# PCB-ARD-DUEBOS.net
KiCad netlist of a schematic drawn in EAGLE
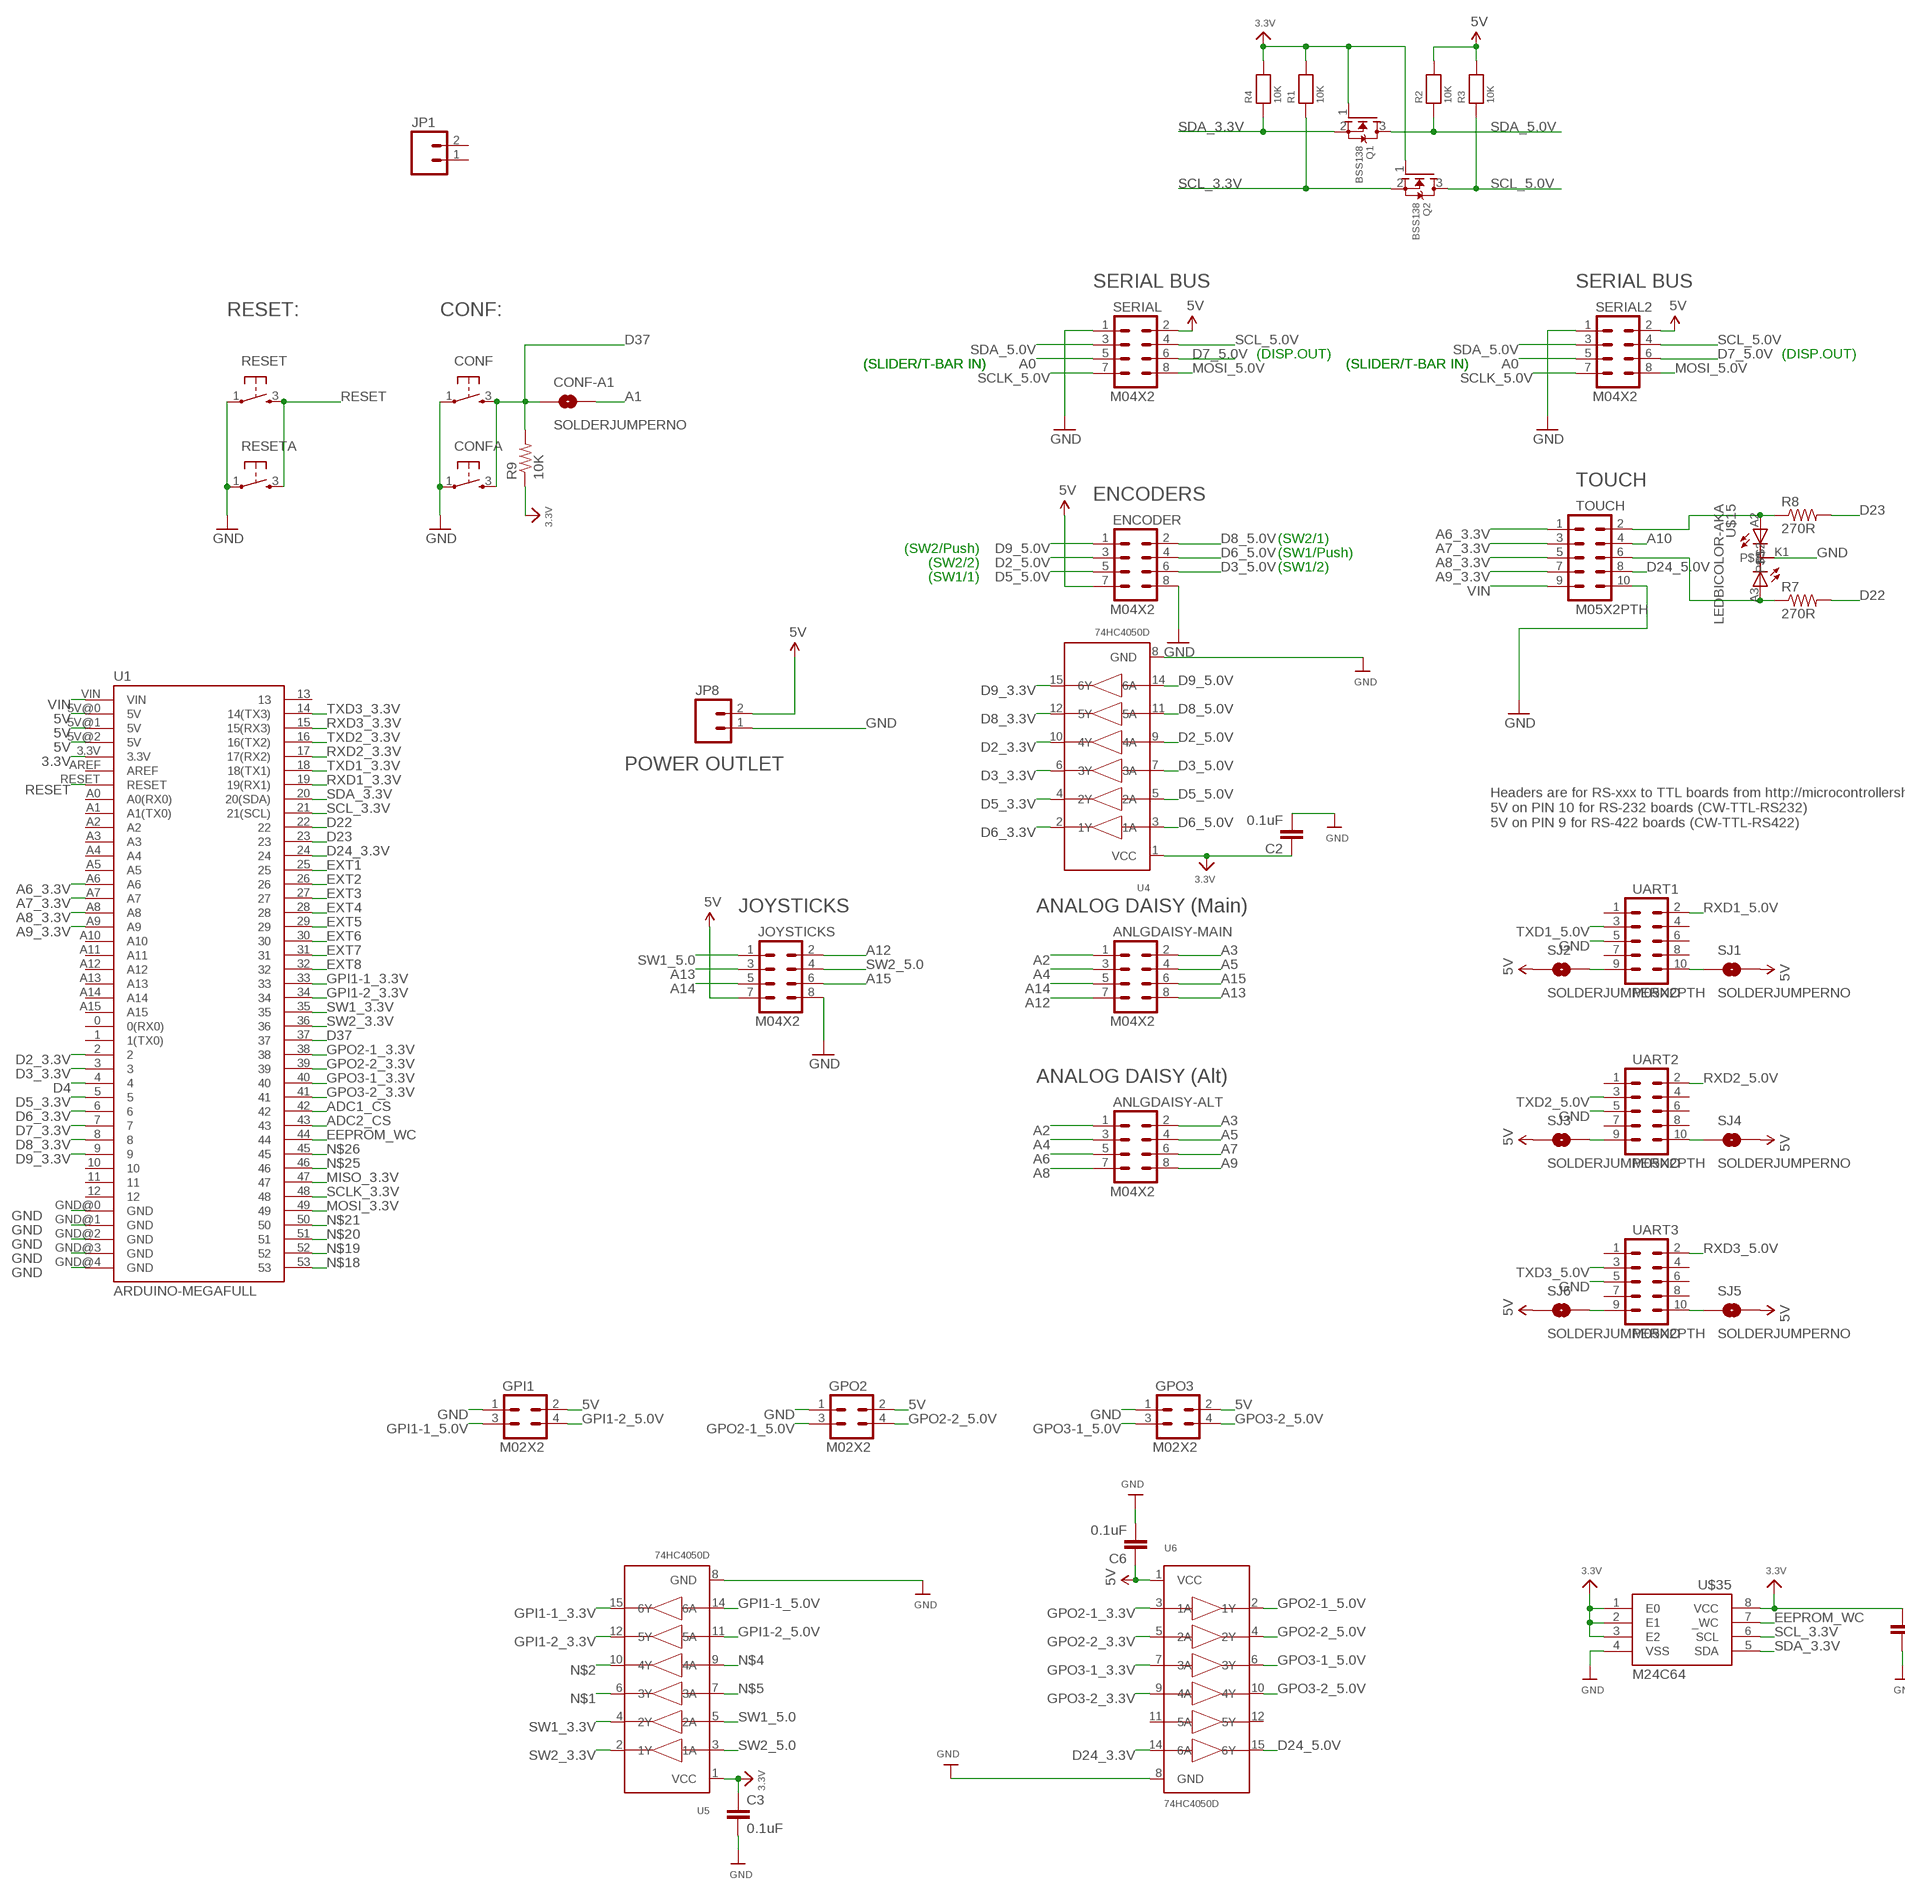
[diagram p0: schematic, sheet 1, part 1 of 2]
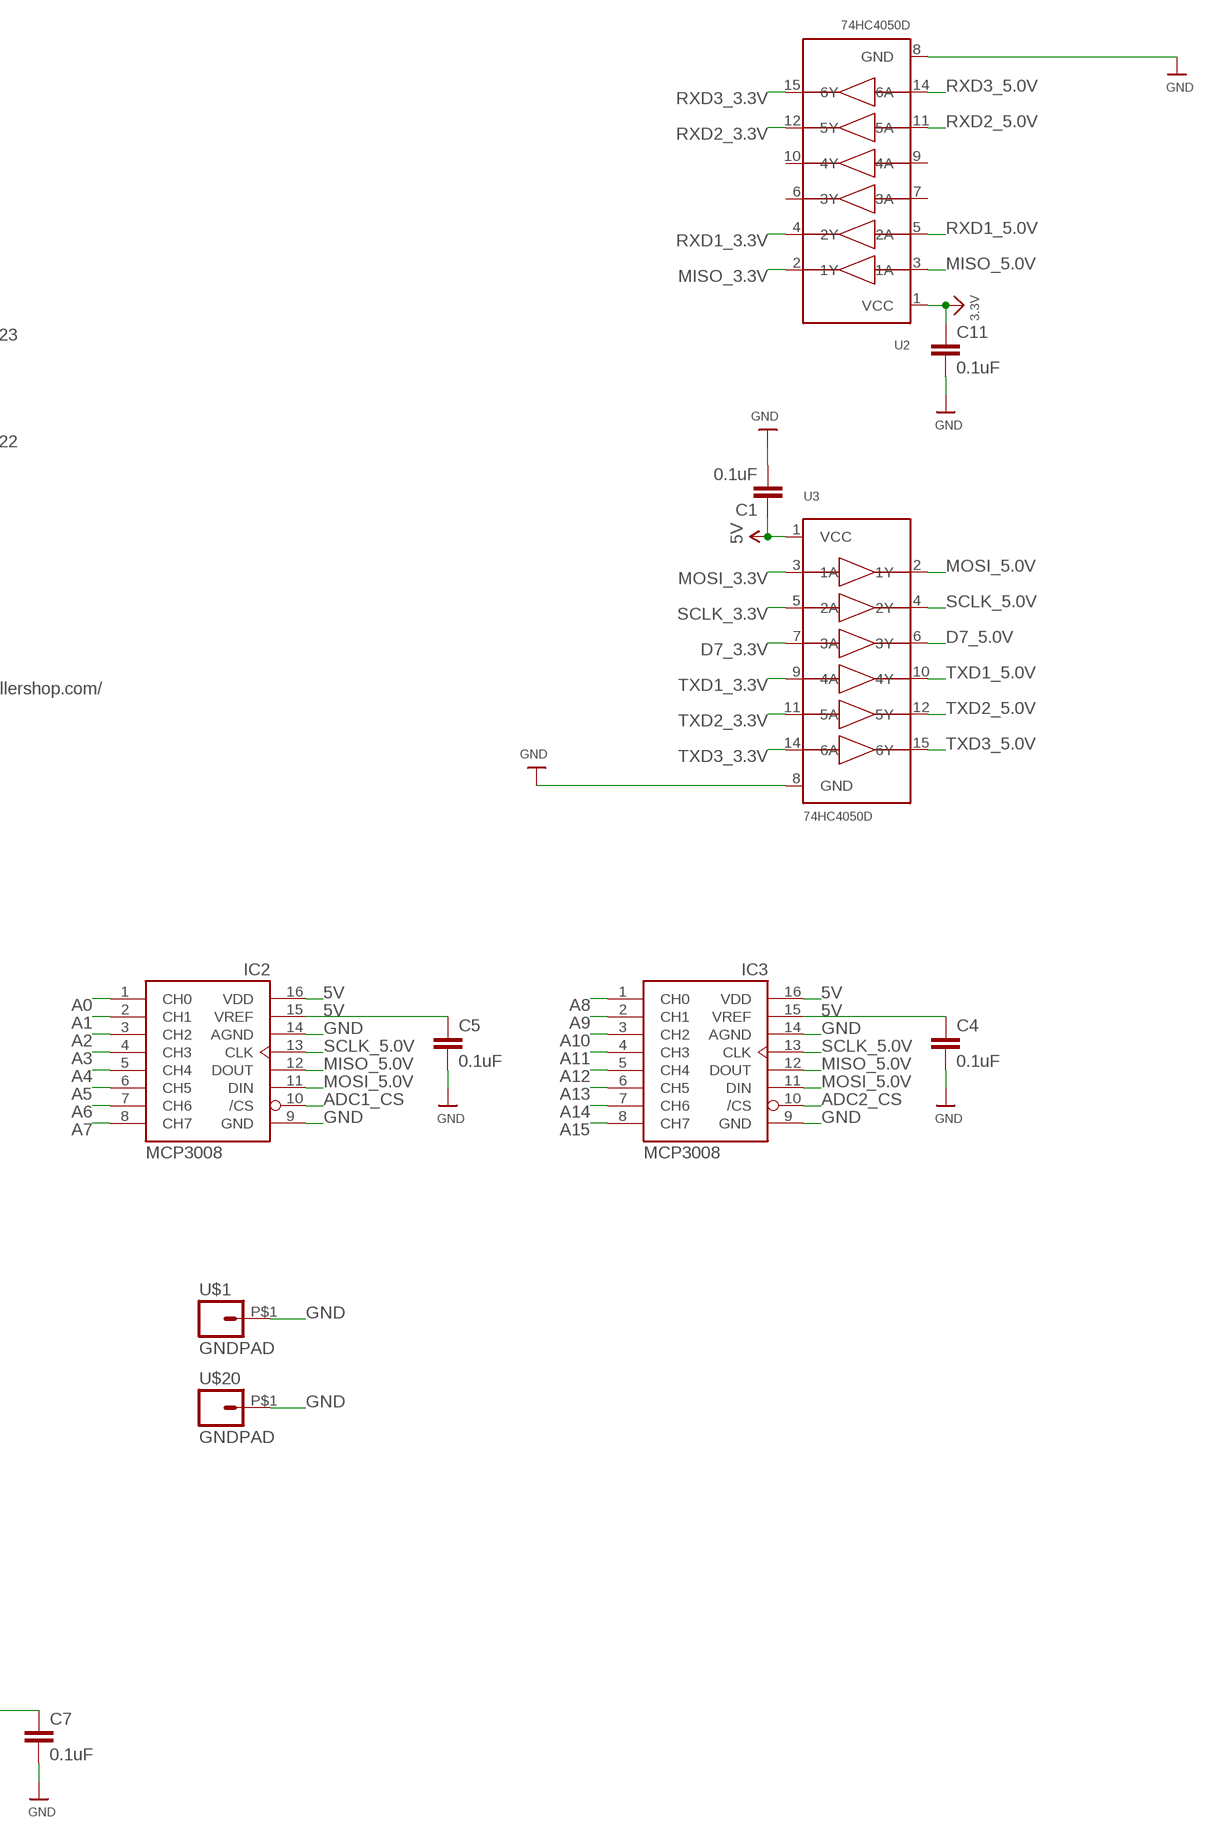
[diagram p1: schematic, sheet 1, part 2 of 2]

(export (version "E")
  (design (tool "Eeschema 10.0.6"))
  (components
    (comp (ref "ANLGDAISY-ALT")
      (value "M04X2")
      (footprint "eagle-import:2X4")
      (libsource (lib "eagle-import") (part "M04X2"))
    )
    (comp (ref "ANLGDAISY-MAIN")
      (value "M04X2")
      (footprint "eagle-import:2X4")
      (libsource (lib "eagle-import") (part "M04X2"))
    )
    (comp (ref "C1")
      (value "0.1uF")
      (footprint "eagle-import:0603-CAP")
      (libsource (lib "eagle-import") (part "CAP0603-CAP"))
    )
    (comp (ref "C2")
      (value "0.1uF")
      (footprint "eagle-import:0603-CAP")
      (libsource (lib "eagle-import") (part "CAP0603-CAP"))
    )
    (comp (ref "C3")
      (value "0.1uF")
      (footprint "eagle-import:0603-CAP")
      (libsource (lib "eagle-import") (part "CAP0603-CAP"))
    )
    (comp (ref "C4")
      (value "0.1uF")
      (footprint "eagle-import:0603-CAP")
      (libsource (lib "eagle-import") (part "CAP0603-CAP"))
    )
    (comp (ref "C5")
      (value "0.1uF")
      (footprint "eagle-import:0603-CAP")
      (libsource (lib "eagle-import") (part "CAP0603-CAP"))
    )
    (comp (ref "C6")
      (value "0.1uF")
      (footprint "eagle-import:0603-CAP")
      (libsource (lib "eagle-import") (part "CAP0603-CAP"))
    )
    (comp (ref "C7")
      (value "0.1uF")
      (footprint "eagle-import:0603-CAP")
      (libsource (lib "eagle-import") (part "CAP0603-CAP"))
    )
    (comp (ref "C11")
      (value "0.1uF")
      (footprint "eagle-import:0603-CAP")
      (libsource (lib "eagle-import") (part "CAP0603-CAP"))
    )
    (comp (ref "CONF")
      (value "TAC_SWITCH")
      (footprint "eagle-import:PUSHBUTTON")
      (libsource (lib "eagle-import") (part "TAC_SWITCH"))
    )
    (comp (ref "CONF-A1")
      (value "SOLDERJUMPERNO")
      (footprint "eagle-import:SJ_2S-NO")
      (libsource (lib "eagle-import") (part "SOLDERJUMPERNO"))
    )
    (comp (ref "CONFA")
      (value "TAC_SWITCH")
      (footprint "eagle-import:PUSHBUTTON")
      (libsource (lib "eagle-import") (part "TAC_SWITCH"))
    )
    (comp (ref "ENCODER")
      (value "M04X2")
      (footprint "eagle-import:2X4")
      (libsource (lib "eagle-import") (part "M04X2"))
    )
    (comp (ref "GPI1")
      (value "M02X2")
      (footprint "eagle-import:2X2")
      (libsource (lib "eagle-import") (part "M02X2"))
    )
    (comp (ref "GPO2")
      (value "M02X2")
      (footprint "eagle-import:2X2")
      (libsource (lib "eagle-import") (part "M02X2"))
    )
    (comp (ref "GPO3")
      (value "M02X2")
      (footprint "eagle-import:2X2")
      (libsource (lib "eagle-import") (part "M02X2"))
    )
    (comp (ref "IC2")
      (value "MCP3008SOIC")
      (footprint "eagle-import:SOIC16")
      (libsource (lib "eagle-import") (part "MCP3008SOIC"))
    )
    (comp (ref "IC3")
      (value "MCP3008SOIC")
      (footprint "eagle-import:SOIC16")
      (libsource (lib "eagle-import") (part "MCP3008SOIC"))
    )
    (comp (ref "JOYSTICKS")
      (value "M04X2")
      (footprint "eagle-import:2X4")
      (libsource (lib "eagle-import") (part "M04X2"))
    )
    (comp (ref "JP1")
      (value "M02PTH")
      (footprint "eagle-import:1X02")
      (libsource (lib "eagle-import") (part "M02PTH"))
    )
    (comp (ref "JP8")
      (value "M02PTH4")
      (footprint "eagle-import:1X02_XTRA_BIG")
      (libsource (lib "eagle-import") (part "M02PTH4"))
    )
    (comp (ref "Q1")
      (value "BSS138")
      (footprint "eagle-import:SOT23-WIDE")
      (libsource (lib "eagle-import") (part "MOSFET-NWIDE"))
    )
    (comp (ref "Q2")
      (value "BSS138")
      (footprint "eagle-import:SOT23-WIDE")
      (libsource (lib "eagle-import") (part "MOSFET-NWIDE"))
    )
    (comp (ref "R1")
      (value "10K")
      (footprint "eagle-import:0805")
      (libsource (lib "eagle-import") (part "RESISTOR0805"))
    )
    (comp (ref "R2")
      (value "10K")
      (footprint "eagle-import:0805")
      (libsource (lib "eagle-import") (part "RESISTOR0805"))
    )
    (comp (ref "R3")
      (value "10K")
      (footprint "eagle-import:0805")
      (libsource (lib "eagle-import") (part "RESISTOR0805"))
    )
    (comp (ref "R4")
      (value "10K")
      (footprint "eagle-import:0805")
      (libsource (lib "eagle-import") (part "RESISTOR0805"))
    )
    (comp (ref "R7")
      (value "270R")
      (footprint "eagle-import:0603-RES")
      (libsource (lib "eagle-import") (part "RESISTOR0603-RES"))
    )
    (comp (ref "R8")
      (value "270R")
      (footprint "eagle-import:0603-RES")
      (libsource (lib "eagle-import") (part "RESISTOR0603-RES"))
    )
    (comp (ref "R9")
      (value "10K")
      (footprint "eagle-import:0603-RES")
      (libsource (lib "eagle-import") (part "RESISTOR0603-RES"))
    )
    (comp (ref "RESET")
      (value "TAC_SWITCH")
      (footprint "eagle-import:PUSHBUTTON")
      (libsource (lib "eagle-import") (part "TAC_SWITCH"))
    )
    (comp (ref "RESETA")
      (value "TAC_SWITCH")
      (footprint "eagle-import:PUSHBUTTON")
      (libsource (lib "eagle-import") (part "TAC_SWITCH"))
    )
    (comp (ref "SERIAL")
      (value "M04X2")
      (footprint "eagle-import:2X4")
      (libsource (lib "eagle-import") (part "M04X2"))
    )
    (comp (ref "SERIAL2")
      (value "M04X2")
      (footprint "eagle-import:2X4")
      (libsource (lib "eagle-import") (part "M04X2"))
    )
    (comp (ref "SJ1")
      (value "SOLDERJUMPERNO")
      (footprint "eagle-import:SJ_2S-NO")
      (libsource (lib "eagle-import") (part "SOLDERJUMPERNO"))
    )
    (comp (ref "SJ2")
      (value "SOLDERJUMPERNO")
      (footprint "eagle-import:SJ_2S-NO")
      (libsource (lib "eagle-import") (part "SOLDERJUMPERNO"))
    )
    (comp (ref "SJ3")
      (value "SOLDERJUMPERNO")
      (footprint "eagle-import:SJ_2S-NO")
      (libsource (lib "eagle-import") (part "SOLDERJUMPERNO"))
    )
    (comp (ref "SJ4")
      (value "SOLDERJUMPERNO")
      (footprint "eagle-import:SJ_2S-NO")
      (libsource (lib "eagle-import") (part "SOLDERJUMPERNO"))
    )
    (comp (ref "SJ5")
      (value "SOLDERJUMPERNO")
      (footprint "eagle-import:SJ_2S-NO")
      (libsource (lib "eagle-import") (part "SOLDERJUMPERNO"))
    )
    (comp (ref "SJ6")
      (value "SOLDERJUMPERNO")
      (footprint "eagle-import:SJ_2S-NO")
      (libsource (lib "eagle-import") (part "SOLDERJUMPERNO"))
    )
    (comp (ref "TOUCH")
      (value "M05X2PTH")
      (footprint "eagle-import:AVR_ICSP")
      (libsource (lib "eagle-import") (part "M05X2PTH"))
    )
    (comp (ref "U$1")
      (value "GNDPAD")
      (footprint "eagle-import:3.2MMPAD")
      (libsource (lib "eagle-import") (part "GNDPAD"))
    )
    (comp (ref "U$15")
      (value "LEDBICOLOR-AKA")
      (footprint "eagle-import:LED5MM-BICOLOR")
      (libsource (lib "eagle-import") (part "LEDBICOLOR-AKA"))
    )
    (comp (ref "U$20")
      (value "GNDPAD")
      (footprint "eagle-import:3.2MMPAD")
      (libsource (lib "eagle-import") (part "GNDPAD"))
    )
    (comp (ref "U$35")
      (value "M24C64")
      (footprint "eagle-import:TSSOP8")
      (libsource (lib "eagle-import") (part "M24C64"))
    )
    (comp (ref "U1")
      (value "ARDUINO-MEGAFULL")
      (footprint "eagle-import:ARDUINO_MEGA")
      (libsource (lib "eagle-import") (part "ARDUINO-MEGAFULL"))
    )
    (comp (ref "U2")
      (value "74HC4050D")
      (footprint "eagle-import:TSSOP16")
      (libsource (lib "eagle-import") (part "74HC4050DTSSOP16"))
    )
    (comp (ref "U3")
      (value "74HC4050D")
      (footprint "eagle-import:TSSOP16")
      (libsource (lib "eagle-import") (part "74HC4050DTSSOP16"))
    )
    (comp (ref "U4")
      (value "74HC4050D")
      (footprint "eagle-import:TSSOP16")
      (libsource (lib "eagle-import") (part "74HC4050DTSSOP16"))
    )
    (comp (ref "U5")
      (value "74HC4050D")
      (footprint "eagle-import:TSSOP16")
      (libsource (lib "eagle-import") (part "74HC4050DTSSOP16"))
    )
    (comp (ref "U6")
      (value "74HC4050D")
      (footprint "eagle-import:TSSOP16")
      (libsource (lib "eagle-import") (part "74HC4050DTSSOP16"))
    )
    (comp (ref "UART1")
      (value "M05X2PTH")
      (footprint "eagle-import:AVR_ICSP")
      (libsource (lib "eagle-import") (part "M05X2PTH"))
    )
    (comp (ref "UART2")
      (value "M05X2PTH")
      (footprint "eagle-import:AVR_ICSP")
      (libsource (lib "eagle-import") (part "M05X2PTH"))
    )
    (comp (ref "UART3")
      (value "M05X2PTH")
      (footprint "eagle-import:AVR_ICSP")
      (libsource (lib "eagle-import") (part "M05X2PTH"))
    )
  )
  (nets
    (net (code "1") (name "/A0") (class "Default")
      (node (ref "IC2") (pin "1") (pinfunction "CH0_1") (pintype "input"))
      (node (ref "SERIAL") (pin "5") (pinfunction "5_5") (pintype "passive"))
      (node (ref "SERIAL2") (pin "5") (pinfunction "5_5") (pintype "passive"))
    )
    (net (code "2") (name "/A1") (class "Default")
      (node (ref "CONF-A1") (pin "2") (pinfunction "2_2") (pintype "passive"))
      (node (ref "IC2") (pin "2") (pinfunction "CH1_2") (pintype "input"))
    )
    (net (code "3") (name "/A2") (class "Default")
      (node (ref "ANLGDAISY-ALT") (pin "1") (pinfunction "1_1") (pintype "passive"))
      (node (ref "ANLGDAISY-MAIN") (pin "1") (pinfunction "1_1") (pintype "passive"))
      (node (ref "IC2") (pin "3") (pinfunction "CH2_3") (pintype "input"))
    )
    (net (code "4") (name "/A3") (class "Default")
      (node (ref "ANLGDAISY-ALT") (pin "2") (pinfunction "2_2") (pintype "passive"))
      (node (ref "ANLGDAISY-MAIN") (pin "2") (pinfunction "2_2") (pintype "passive"))
      (node (ref "IC2") (pin "4") (pinfunction "CH3_4") (pintype "input"))
    )
    (net (code "5") (name "/A4") (class "Default")
      (node (ref "ANLGDAISY-ALT") (pin "3") (pinfunction "3_3") (pintype "passive"))
      (node (ref "ANLGDAISY-MAIN") (pin "3") (pinfunction "3_3") (pintype "passive"))
      (node (ref "IC2") (pin "5") (pinfunction "CH4_5") (pintype "input"))
    )
    (net (code "6") (name "/A5") (class "Default")
      (node (ref "ANLGDAISY-ALT") (pin "4") (pinfunction "4_4") (pintype "passive"))
      (node (ref "ANLGDAISY-MAIN") (pin "4") (pinfunction "4_4") (pintype "passive"))
      (node (ref "IC2") (pin "6") (pinfunction "CH5_6") (pintype "input"))
    )
    (net (code "7") (name "/A6") (class "Default")
      (node (ref "ANLGDAISY-ALT") (pin "5") (pinfunction "5_5") (pintype "passive"))
      (node (ref "IC2") (pin "7") (pinfunction "CH6_7") (pintype "input"))
    )
    (net (code "8") (name "/A6_3.3V") (class "Default")
      (node (ref "TOUCH") (pin "1") (pinfunction "1_1") (pintype "passive"))
      (node (ref "U1") (pin "A6") (pinfunction "A6_A6") (pintype "bidirectional"))
    )
    (net (code "9") (name "/A7") (class "Default")
      (node (ref "ANLGDAISY-ALT") (pin "6") (pinfunction "6_6") (pintype "passive"))
      (node (ref "IC2") (pin "8") (pinfunction "CH7_8") (pintype "input"))
    )
    (net (code "10") (name "/A7_3.3V") (class "Default")
      (node (ref "TOUCH") (pin "3") (pinfunction "3_3") (pintype "passive"))
      (node (ref "U1") (pin "A7") (pinfunction "A7_A7") (pintype "bidirectional"))
    )
    (net (code "11") (name "/A8") (class "Default")
      (node (ref "ANLGDAISY-ALT") (pin "7") (pinfunction "7_7") (pintype "passive"))
      (node (ref "IC3") (pin "1") (pinfunction "CH0_1") (pintype "input"))
    )
    (net (code "12") (name "/A8_3.3V") (class "Default")
      (node (ref "TOUCH") (pin "5") (pinfunction "5_5") (pintype "passive"))
      (node (ref "U1") (pin "A8") (pinfunction "A8_A8") (pintype "bidirectional"))
    )
    (net (code "13") (name "/A9") (class "Default")
      (node (ref "ANLGDAISY-ALT") (pin "8") (pinfunction "8_8") (pintype "passive"))
      (node (ref "IC3") (pin "2") (pinfunction "CH1_2") (pintype "input"))
    )
    (net (code "14") (name "/A9_3.3V") (class "Default")
      (node (ref "TOUCH") (pin "7") (pinfunction "7_7") (pintype "passive"))
      (node (ref "U1") (pin "A9") (pinfunction "A9_A9") (pintype "bidirectional"))
    )
    (net (code "15") (name "/A10") (class "Default")
      (node (ref "IC3") (pin "3") (pinfunction "CH2_3") (pintype "input"))
      (node (ref "TOUCH") (pin "4") (pinfunction "4_4") (pintype "passive"))
    )
    (net (code "16") (name "/A11") (class "Default")
      (node (ref "IC3") (pin "4") (pinfunction "CH3_4") (pintype "input"))
    )
    (net (code "17") (name "/A12") (class "Default")
      (node (ref "ANLGDAISY-MAIN") (pin "7") (pinfunction "7_7") (pintype "passive"))
      (node (ref "IC3") (pin "5") (pinfunction "CH4_5") (pintype "input"))
      (node (ref "JOYSTICKS") (pin "2") (pinfunction "2_2") (pintype "passive"))
    )
    (net (code "18") (name "/A13") (class "Default")
      (node (ref "ANLGDAISY-MAIN") (pin "8") (pinfunction "8_8") (pintype "passive"))
      (node (ref "IC3") (pin "6") (pinfunction "CH5_6") (pintype "input"))
      (node (ref "JOYSTICKS") (pin "3") (pinfunction "3_3") (pintype "passive"))
    )
    (net (code "19") (name "/A14") (class "Default")
      (node (ref "ANLGDAISY-MAIN") (pin "5") (pinfunction "5_5") (pintype "passive"))
      (node (ref "IC3") (pin "7") (pinfunction "CH6_7") (pintype "input"))
      (node (ref "JOYSTICKS") (pin "5") (pinfunction "5_5") (pintype "passive"))
    )
    (net (code "20") (name "/A15") (class "Default")
      (node (ref "ANLGDAISY-MAIN") (pin "6") (pinfunction "6_6") (pintype "passive"))
      (node (ref "IC3") (pin "8") (pinfunction "CH7_8") (pintype "input"))
      (node (ref "JOYSTICKS") (pin "6") (pinfunction "6_6") (pintype "passive"))
    )
    (net (code "21") (name "/ADC1_CS") (class "Default")
      (node (ref "IC2") (pin "10") (pinfunction "/CS_10") (pintype "input"))
      (node (ref "U1") (pin "42") (pinfunction "42_42") (pintype "bidirectional"))
    )
    (net (code "22") (name "/ADC2_CS") (class "Default")
      (node (ref "IC3") (pin "10") (pinfunction "/CS_10") (pintype "input"))
      (node (ref "U1") (pin "43") (pinfunction "43_43") (pintype "bidirectional"))
    )
    (net (code "23") (name "/D2_3.3V") (class "Default")
      (node (ref "U1") (pin "2") (pinfunction "2_2") (pintype "bidirectional"))
      (node (ref "U4") (pin "10") (pinfunction "4Y_10") (pintype "bidirectional"))
    )
    (net (code "24") (name "/D2_5.0V") (class "Default")
      (node (ref "ENCODER") (pin "3") (pinfunction "3_3") (pintype "passive"))
      (node (ref "U4") (pin "9") (pinfunction "4A_9") (pintype "bidirectional"))
    )
    (net (code "25") (name "/D3_3.3V") (class "Default")
      (node (ref "U1") (pin "3") (pinfunction "3_3") (pintype "bidirectional"))
      (node (ref "U4") (pin "6") (pinfunction "3Y_6") (pintype "bidirectional"))
    )
    (net (code "26") (name "/D3_5.0V") (class "Default")
      (node (ref "ENCODER") (pin "6") (pinfunction "6_6") (pintype "passive"))
      (node (ref "U4") (pin "7") (pinfunction "3A_7") (pintype "bidirectional"))
    )
    (net (code "27") (name "/D4") (class "Default")
      (node (ref "U1") (pin "4") (pinfunction "4_4") (pintype "bidirectional"))
    )
    (net (code "28") (name "/D5_3.3V") (class "Default")
      (node (ref "U1") (pin "5") (pinfunction "5_5") (pintype "bidirectional"))
      (node (ref "U4") (pin "4") (pinfunction "2Y_4") (pintype "bidirectional"))
    )
    (net (code "29") (name "/D5_5.0V") (class "Default")
      (node (ref "ENCODER") (pin "5") (pinfunction "5_5") (pintype "passive"))
      (node (ref "U4") (pin "5") (pinfunction "2A_5") (pintype "bidirectional"))
    )
    (net (code "30") (name "/D6_3.3V") (class "Default")
      (node (ref "U1") (pin "6") (pinfunction "6_6") (pintype "bidirectional"))
      (node (ref "U4") (pin "2") (pinfunction "1Y_2") (pintype "bidirectional"))
    )
    (net (code "31") (name "/D6_5.0V") (class "Default")
      (node (ref "ENCODER") (pin "4") (pinfunction "4_4") (pintype "passive"))
      (node (ref "U4") (pin "3") (pinfunction "1A_3") (pintype "bidirectional"))
    )
    (net (code "32") (name "/D7_3.3V") (class "Default")
      (node (ref "U1") (pin "7") (pinfunction "7_7") (pintype "bidirectional"))
      (node (ref "U3") (pin "7") (pinfunction "3A_7") (pintype "bidirectional"))
    )
    (net (code "33") (name "/D7_5.0V") (class "Default")
      (node (ref "SERIAL") (pin "6") (pinfunction "6_6") (pintype "passive"))
      (node (ref "SERIAL2") (pin "6") (pinfunction "6_6") (pintype "passive"))
      (node (ref "U3") (pin "6") (pinfunction "3Y_6") (pintype "bidirectional"))
    )
    (net (code "34") (name "/D8_3.3V") (class "Default")
      (node (ref "U1") (pin "8") (pinfunction "8_8") (pintype "bidirectional"))
      (node (ref "U4") (pin "12") (pinfunction "5Y_12") (pintype "bidirectional"))
    )
    (net (code "35") (name "/D8_5.0V") (class "Default")
      (node (ref "ENCODER") (pin "2") (pinfunction "2_2") (pintype "passive"))
      (node (ref "U4") (pin "11") (pinfunction "5A_11") (pintype "bidirectional"))
    )
    (net (code "36") (name "/D9_3.3V") (class "Default")
      (node (ref "U1") (pin "9") (pinfunction "9_9") (pintype "bidirectional"))
      (node (ref "U4") (pin "15") (pinfunction "6Y_15") (pintype "bidirectional"))
    )
    (net (code "37") (name "/D9_5.0V") (class "Default")
      (node (ref "ENCODER") (pin "1") (pinfunction "1_1") (pintype "passive"))
      (node (ref "U4") (pin "14") (pinfunction "6A_14") (pintype "bidirectional"))
    )
    (net (code "38") (name "/D22") (class "Default")
      (node (ref "R7") (pin "2") (pinfunction "2_2") (pintype "passive"))
      (node (ref "U1") (pin "22") (pinfunction "22_22") (pintype "bidirectional"))
    )
    (net (code "39") (name "/D23") (class "Default")
      (node (ref "R8") (pin "2") (pinfunction "2_2") (pintype "passive"))
      (node (ref "U1") (pin "23") (pinfunction "23_23") (pintype "bidirectional"))
    )
    (net (code "40") (name "/D24_3.3V") (class "Default")
      (node (ref "U1") (pin "24") (pinfunction "24_24") (pintype "bidirectional"))
      (node (ref "U6") (pin "14") (pinfunction "6A_14") (pintype "bidirectional"))
    )
    (net (code "41") (name "/D24_5.0V") (class "Default")
      (node (ref "TOUCH") (pin "8") (pinfunction "8_8") (pintype "passive"))
      (node (ref "U6") (pin "15") (pinfunction "6Y_15") (pintype "bidirectional"))
    )
    (net (code "42") (name "/D37") (class "Default")
      (node (ref "CONF") (pin "3") (pinfunction "3_3") (pintype "passive"))
      (node (ref "CONF-A1") (pin "1") (pinfunction "1_1") (pintype "passive"))
      (node (ref "CONFA") (pin "3") (pinfunction "3_3") (pintype "passive"))
      (node (ref "R9") (pin "2") (pinfunction "2_2") (pintype "passive"))
      (node (ref "U1") (pin "37") (pinfunction "37_37") (pintype "bidirectional"))
    )
    (net (code "43") (name "/EEPROM_WC") (class "Default")
      (node (ref "U$35") (pin "7") (pinfunction "_WC_7") (pintype "bidirectional"))
      (node (ref "U1") (pin "44") (pinfunction "44_44") (pintype "bidirectional"))
    )
    (net (code "44") (name "/EXT1") (class "Default")
      (node (ref "U1") (pin "25") (pinfunction "25_25") (pintype "bidirectional"))
    )
    (net (code "45") (name "/EXT2") (class "Default")
      (node (ref "U1") (pin "26") (pinfunction "26_26") (pintype "bidirectional"))
    )
    (net (code "46") (name "/EXT3") (class "Default")
      (node (ref "U1") (pin "27") (pinfunction "27_27") (pintype "bidirectional"))
    )
    (net (code "47") (name "/EXT4") (class "Default")
      (node (ref "U1") (pin "28") (pinfunction "28_28") (pintype "bidirectional"))
    )
    (net (code "48") (name "/EXT5") (class "Default")
      (node (ref "U1") (pin "29") (pinfunction "29_29") (pintype "bidirectional"))
    )
    (net (code "49") (name "/EXT6") (class "Default")
      (node (ref "U1") (pin "30") (pinfunction "30_30") (pintype "bidirectional"))
    )
    (net (code "50") (name "/EXT7") (class "Default")
      (node (ref "U1") (pin "31") (pinfunction "31_31") (pintype "bidirectional"))
    )
    (net (code "51") (name "/EXT8") (class "Default")
      (node (ref "U1") (pin "32") (pinfunction "32_32") (pintype "bidirectional"))
    )
    (net (code "52") (name "/GPI1-1_3.3V") (class "Default")
      (node (ref "U1") (pin "33") (pinfunction "33_33") (pintype "bidirectional"))
      (node (ref "U5") (pin "15") (pinfunction "6Y_15") (pintype "bidirectional"))
    )
    (net (code "53") (name "/GPI1-1_5.0V") (class "Default")
      (node (ref "GPI1") (pin "3") (pinfunction "3_3") (pintype "passive"))
      (node (ref "U5") (pin "14") (pinfunction "6A_14") (pintype "bidirectional"))
    )
    (net (code "54") (name "/GPI1-2_3.3V") (class "Default")
      (node (ref "U1") (pin "34") (pinfunction "34_34") (pintype "bidirectional"))
      (node (ref "U5") (pin "12") (pinfunction "5Y_12") (pintype "bidirectional"))
    )
    (net (code "55") (name "/GPI1-2_5.0V") (class "Default")
      (node (ref "GPI1") (pin "4") (pinfunction "4_4") (pintype "passive"))
      (node (ref "U5") (pin "11") (pinfunction "5A_11") (pintype "bidirectional"))
    )
    (net (code "56") (name "/GPO2-1_3.3V") (class "Default")
      (node (ref "U1") (pin "38") (pinfunction "38_38") (pintype "bidirectional"))
      (node (ref "U6") (pin "3") (pinfunction "1A_3") (pintype "bidirectional"))
    )
    (net (code "57") (name "/GPO2-1_5.0V") (class "Default")
      (node (ref "GPO2") (pin "3") (pinfunction "3_3") (pintype "passive"))
      (node (ref "U6") (pin "2") (pinfunction "1Y_2") (pintype "bidirectional"))
    )
    (net (code "58") (name "/GPO2-2_3.3V") (class "Default")
      (node (ref "U1") (pin "39") (pinfunction "39_39") (pintype "bidirectional"))
      (node (ref "U6") (pin "5") (pinfunction "2A_5") (pintype "bidirectional"))
    )
    (net (code "59") (name "/GPO2-2_5.0V") (class "Default")
      (node (ref "GPO2") (pin "4") (pinfunction "4_4") (pintype "passive"))
      (node (ref "U6") (pin "4") (pinfunction "2Y_4") (pintype "bidirectional"))
    )
    (net (code "60") (name "/GPO3-1_3.3V") (class "Default")
      (node (ref "U1") (pin "40") (pinfunction "40_40") (pintype "bidirectional"))
      (node (ref "U6") (pin "7") (pinfunction "3A_7") (pintype "bidirectional"))
    )
    (net (code "61") (name "/GPO3-1_5.0V") (class "Default")
      (node (ref "GPO3") (pin "3") (pinfunction "3_3") (pintype "passive"))
      (node (ref "U6") (pin "6") (pinfunction "3Y_6") (pintype "bidirectional"))
    )
    (net (code "62") (name "/GPO3-2_3.3V") (class "Default")
      (node (ref "U1") (pin "41") (pinfunction "41_41") (pintype "bidirectional"))
      (node (ref "U6") (pin "9") (pinfunction "4A_9") (pintype "bidirectional"))
    )
    (net (code "63") (name "/GPO3-2_5.0V") (class "Default")
      (node (ref "GPO3") (pin "4") (pinfunction "4_4") (pintype "passive"))
      (node (ref "U6") (pin "10") (pinfunction "4Y_10") (pintype "bidirectional"))
    )
    (net (code "64") (name "/MISO_3.3V") (class "Default")
      (node (ref "U1") (pin "47") (pinfunction "47_47") (pintype "bidirectional"))
      (node (ref "U2") (pin "2") (pinfunction "1Y_2") (pintype "bidirectional"))
    )
    (net (code "65") (name "/MISO_5.0V") (class "Default")
      (node (ref "IC2") (pin "12") (pinfunction "DOUT_12") (pintype "output"))
      (node (ref "IC3") (pin "12") (pinfunction "DOUT_12") (pintype "output"))
      (node (ref "U2") (pin "3") (pinfunction "1A_3") (pintype "bidirectional"))
    )
    (net (code "66") (name "/MOSI_3.3V") (class "Default")
      (node (ref "U1") (pin "49") (pinfunction "49_49") (pintype "bidirectional"))
      (node (ref "U3") (pin "3") (pinfunction "1A_3") (pintype "bidirectional"))
    )
    (net (code "67") (name "/MOSI_5.0V") (class "Default")
      (node (ref "IC2") (pin "11") (pinfunction "DIN_11") (pintype "input"))
      (node (ref "IC3") (pin "11") (pinfunction "DIN_11") (pintype "input"))
      (node (ref "SERIAL") (pin "8") (pinfunction "8_8") (pintype "passive"))
      (node (ref "SERIAL2") (pin "8") (pinfunction "8_8") (pintype "passive"))
      (node (ref "U3") (pin "2") (pinfunction "1Y_2") (pintype "bidirectional"))
    )
    (net (code "68") (name "/N$1") (class "Default")
      (node (ref "U5") (pin "6") (pinfunction "3Y_6") (pintype "bidirectional"))
    )
    (net (code "69") (name "/N$2") (class "Default")
      (node (ref "U5") (pin "10") (pinfunction "4Y_10") (pintype "bidirectional"))
    )
    (net (code "70") (name "/N$4") (class "Default")
      (node (ref "U5") (pin "9") (pinfunction "4A_9") (pintype "bidirectional"))
    )
    (net (code "71") (name "/N$5") (class "Default")
      (node (ref "U5") (pin "7") (pinfunction "3A_7") (pintype "bidirectional"))
    )
    (net (code "72") (name "/N$18") (class "Default")
      (node (ref "U1") (pin "53") (pinfunction "53_53") (pintype "bidirectional"))
    )
    (net (code "73") (name "/N$19") (class "Default")
      (node (ref "U1") (pin "52") (pinfunction "52_52") (pintype "bidirectional"))
    )
    (net (code "74") (name "/N$20") (class "Default")
      (node (ref "U1") (pin "51") (pinfunction "51_51") (pintype "bidirectional"))
    )
    (net (code "75") (name "/N$21") (class "Default")
      (node (ref "U1") (pin "50") (pinfunction "50_50") (pintype "bidirectional"))
    )
    (net (code "76") (name "/N$25") (class "Default")
      (node (ref "U1") (pin "46") (pinfunction "46_46") (pintype "bidirectional"))
    )
    (net (code "77") (name "/N$26") (class "Default")
      (node (ref "U1") (pin "45") (pinfunction "45_45") (pintype "bidirectional"))
    )
    (net (code "78") (name "/RESET") (class "Default")
      (node (ref "RESET") (pin "3") (pinfunction "3_3") (pintype "passive"))
      (node (ref "RESETA") (pin "3") (pinfunction "3_3") (pintype "passive"))
      (node (ref "U1") (pin "RESET") (pinfunction "RESET_RESET") (pintype "bidirectional"))
    )
    (net (code "79") (name "/RXD1_3.3V") (class "Default")
      (node (ref "U1") (pin "19") (pinfunction "19(RX1)_19") (pintype "bidirectional"))
      (node (ref "U2") (pin "4") (pinfunction "2Y_4") (pintype "bidirectional"))
    )
    (net (code "80") (name "/RXD1_5.0V") (class "Default")
      (node (ref "U2") (pin "5") (pinfunction "2A_5") (pintype "bidirectional"))
      (node (ref "UART1") (pin "2") (pinfunction "2_2") (pintype "passive"))
    )
    (net (code "81") (name "/RXD2_3.3V") (class "Default")
      (node (ref "U1") (pin "17") (pinfunction "17(RX2)_17") (pintype "bidirectional"))
      (node (ref "U2") (pin "12") (pinfunction "5Y_12") (pintype "bidirectional"))
    )
    (net (code "82") (name "/RXD2_5.0V") (class "Default")
      (node (ref "U2") (pin "11") (pinfunction "5A_11") (pintype "bidirectional"))
      (node (ref "UART2") (pin "2") (pinfunction "2_2") (pintype "passive"))
    )
    (net (code "83") (name "/RXD3_3.3V") (class "Default")
      (node (ref "U1") (pin "15") (pinfunction "15(RX3)_15") (pintype "bidirectional"))
      (node (ref "U2") (pin "15") (pinfunction "6Y_15") (pintype "bidirectional"))
    )
    (net (code "84") (name "/RXD3_5.0V") (class "Default")
      (node (ref "U2") (pin "14") (pinfunction "6A_14") (pintype "bidirectional"))
      (node (ref "UART3") (pin "2") (pinfunction "2_2") (pintype "passive"))
    )
    (net (code "85") (name "/SCLK_3.3V") (class "Default")
      (node (ref "U1") (pin "48") (pinfunction "48_48") (pintype "bidirectional"))
      (node (ref "U3") (pin "5") (pinfunction "2A_5") (pintype "bidirectional"))
    )
    (net (code "86") (name "/SCLK_5.0V") (class "Default")
      (node (ref "IC2") (pin "13") (pinfunction "CLK_13") (pintype "input"))
      (node (ref "IC3") (pin "13") (pinfunction "CLK_13") (pintype "input"))
      (node (ref "SERIAL") (pin "7") (pinfunction "7_7") (pintype "passive"))
      (node (ref "SERIAL2") (pin "7") (pinfunction "7_7") (pintype "passive"))
      (node (ref "U3") (pin "4") (pinfunction "2Y_4") (pintype "bidirectional"))
    )
    (net (code "87") (name "/SCL_3.3V") (class "Default")
      (node (ref "Q2") (pin "2") (pinfunction "S_2") (pintype "bidirectional"))
      (node (ref "R1") (pin "1") (pinfunction "1_1") (pintype "passive"))
      (node (ref "U$35") (pin "6") (pinfunction "SCL_6") (pintype "bidirectional"))
      (node (ref "U1") (pin "21") (pinfunction "21(SCL)_21") (pintype "bidirectional"))
    )
    (net (code "88") (name "/SCL_5.0V") (class "Default")
      (node (ref "Q2") (pin "3") (pinfunction "D_3") (pintype "bidirectional"))
      (node (ref "R3") (pin "1") (pinfunction "1_1") (pintype "passive"))
      (node (ref "SERIAL") (pin "4") (pinfunction "4_4") (pintype "passive"))
      (node (ref "SERIAL2") (pin "4") (pinfunction "4_4") (pintype "passive"))
    )
    (net (code "89") (name "/SDA_3.3V") (class "Default")
      (node (ref "Q1") (pin "2") (pinfunction "S_2") (pintype "bidirectional"))
      (node (ref "R4") (pin "1") (pinfunction "1_1") (pintype "passive"))
      (node (ref "U$35") (pin "5") (pinfunction "SDA_5") (pintype "bidirectional"))
      (node (ref "U1") (pin "20") (pinfunction "20(SDA)_20") (pintype "bidirectional"))
    )
    (net (code "90") (name "/SDA_5.0V") (class "Default")
      (node (ref "Q1") (pin "3") (pinfunction "D_3") (pintype "bidirectional"))
      (node (ref "R2") (pin "1") (pinfunction "1_1") (pintype "passive"))
      (node (ref "SERIAL") (pin "3") (pinfunction "3_3") (pintype "passive"))
      (node (ref "SERIAL2") (pin "3") (pinfunction "3_3") (pintype "passive"))
    )
    (net (code "91") (name "/SW1_3.3V") (class "Default")
      (node (ref "U1") (pin "35") (pinfunction "35_35") (pintype "bidirectional"))
      (node (ref "U5") (pin "4") (pinfunction "2Y_4") (pintype "bidirectional"))
    )
    (net (code "92") (name "/SW1_5.0") (class "Default")
      (node (ref "JOYSTICKS") (pin "1") (pinfunction "1_1") (pintype "passive"))
      (node (ref "U5") (pin "5") (pinfunction "2A_5") (pintype "bidirectional"))
    )
    (net (code "93") (name "/SW2_3.3V") (class "Default")
      (node (ref "U1") (pin "36") (pinfunction "36_36") (pintype "bidirectional"))
      (node (ref "U5") (pin "2") (pinfunction "1Y_2") (pintype "bidirectional"))
    )
    (net (code "94") (name "/SW2_5.0") (class "Default")
      (node (ref "JOYSTICKS") (pin "4") (pinfunction "4_4") (pintype "passive"))
      (node (ref "U5") (pin "3") (pinfunction "1A_3") (pintype "bidirectional"))
    )
    (net (code "95") (name "/TXD1_3.3V") (class "Default")
      (node (ref "U1") (pin "18") (pinfunction "18(TX1)_18") (pintype "bidirectional"))
      (node (ref "U3") (pin "9") (pinfunction "4A_9") (pintype "bidirectional"))
    )
    (net (code "96") (name "/TXD1_5.0V") (class "Default")
      (node (ref "U3") (pin "10") (pinfunction "4Y_10") (pintype "bidirectional"))
      (node (ref "UART1") (pin "3") (pinfunction "3_3") (pintype "passive"))
    )
    (net (code "97") (name "/TXD2_3.3V") (class "Default")
      (node (ref "U1") (pin "16") (pinfunction "16(TX2)_16") (pintype "bidirectional"))
      (node (ref "U3") (pin "11") (pinfunction "5A_11") (pintype "bidirectional"))
    )
    (net (code "98") (name "/TXD2_5.0V") (class "Default")
      (node (ref "U3") (pin "12") (pinfunction "5Y_12") (pintype "bidirectional"))
      (node (ref "UART2") (pin "3") (pinfunction "3_3") (pintype "passive"))
    )
    (net (code "99") (name "/TXD3_3.3V") (class "Default")
      (node (ref "U1") (pin "14") (pinfunction "14(TX3)_14") (pintype "bidirectional"))
      (node (ref "U3") (pin "14") (pinfunction "6A_14") (pintype "bidirectional"))
    )
    (net (code "100") (name "/TXD3_5.0V") (class "Default")
      (node (ref "U3") (pin "15") (pinfunction "6Y_15") (pintype "bidirectional"))
      (node (ref "UART3") (pin "3") (pinfunction "3_3") (pintype "passive"))
    )
    (net (code "101") (name "/VIN") (class "Default")
      (node (ref "TOUCH") (pin "9") (pinfunction "9_9") (pintype "passive"))
      (node (ref "U1") (pin "VIN") (pinfunction "VIN_VIN") (pintype "bidirectional"))
    )
    (net (code "102") (name "3.3V") (class "Default")
      (node (ref "C11") (pin "1") (pinfunction "1_1") (pintype "passive"))
      (node (ref "C2") (pin "1") (pinfunction "1_1") (pintype "passive"))
      (node (ref "C3") (pin "1") (pinfunction "1_1") (pintype "passive"))
      (node (ref "C7") (pin "1") (pinfunction "1_1") (pintype "passive"))
      (node (ref "Q1") (pin "1") (pinfunction "G_1") (pintype "bidirectional"))
      (node (ref "Q2") (pin "1") (pinfunction "G_1") (pintype "bidirectional"))
      (node (ref "R1") (pin "2") (pinfunction "2_2") (pintype "passive"))
      (node (ref "R4") (pin "2") (pinfunction "2_2") (pintype "passive"))
      (node (ref "R9") (pin "1") (pinfunction "1_1") (pintype "passive"))
      (node (ref "U$35") (pin "1") (pinfunction "E0_1") (pintype "bidirectional"))
      (node (ref "U$35") (pin "2") (pinfunction "E1_2") (pintype "bidirectional"))
      (node (ref "U$35") (pin "3") (pinfunction "E2_3") (pintype "bidirectional"))
      (node (ref "U$35") (pin "8") (pinfunction "VCC_8") (pintype "power_in"))
      (node (ref "U1") (pin "3.3V") (pinfunction "3.3V_3.3V") (pintype "bidirectional"))
      (node (ref "U2") (pin "1") (pinfunction "VCC_1") (pintype "bidirectional"))
      (node (ref "U4") (pin "1") (pinfunction "VCC_1") (pintype "bidirectional"))
      (node (ref "U5") (pin "1") (pinfunction "VCC_1") (pintype "bidirectional"))
    )
    (net (code "103") (name "5V") (class "Default")
      (node (ref "C1") (pin "1") (pinfunction "1_1") (pintype "passive"))
      (node (ref "C4") (pin "1") (pinfunction "1_1") (pintype "passive"))
      (node (ref "C5") (pin "1") (pinfunction "1_1") (pintype "passive"))
      (node (ref "C6") (pin "1") (pinfunction "1_1") (pintype "passive"))
      (node (ref "ENCODER") (pin "7") (pinfunction "7_7") (pintype "passive"))
      (node (ref "GPI1") (pin "2") (pinfunction "2_2") (pintype "passive"))
      (node (ref "GPO2") (pin "2") (pinfunction "2_2") (pintype "passive"))
      (node (ref "GPO3") (pin "2") (pinfunction "2_2") (pintype "passive"))
      (node (ref "IC2") (pin "15") (pinfunction "VREF_15") (pintype "input"))
      (node (ref "IC2") (pin "16") (pinfunction "VDD_16") (pintype "power_in"))
      (node (ref "IC3") (pin "15") (pinfunction "VREF_15") (pintype "input"))
      (node (ref "IC3") (pin "16") (pinfunction "VDD_16") (pintype "power_in"))
      (node (ref "JOYSTICKS") (pin "7") (pinfunction "7_7") (pintype "passive"))
      (node (ref "JP8") (pin "2") (pinfunction "2_2") (pintype "passive"))
      (node (ref "R2") (pin "2") (pinfunction "2_2") (pintype "passive"))
      (node (ref "R3") (pin "2") (pinfunction "2_2") (pintype "passive"))
      (node (ref "SERIAL") (pin "2") (pinfunction "2_2") (pintype "passive"))
      (node (ref "SERIAL2") (pin "2") (pinfunction "2_2") (pintype "passive"))
      (node (ref "SJ1") (pin "2") (pinfunction "2_2") (pintype "passive"))
      (node (ref "SJ2") (pin "1") (pinfunction "1_1") (pintype "passive"))
      (node (ref "SJ3") (pin "1") (pinfunction "1_1") (pintype "passive"))
      (node (ref "SJ4") (pin "2") (pinfunction "2_2") (pintype "passive"))
      (node (ref "SJ5") (pin "2") (pinfunction "2_2") (pintype "passive"))
      (node (ref "SJ6") (pin "1") (pinfunction "1_1") (pintype "passive"))
      (node (ref "U1") (pin "5V@0") (pinfunction "5V_5V@0") (pintype "bidirectional"))
      (node (ref "U1") (pin "5V@1") (pinfunction "5V_5V@1") (pintype "bidirectional"))
      (node (ref "U1") (pin "5V@2") (pinfunction "5V_5V@2") (pintype "bidirectional"))
      (node (ref "U3") (pin "1") (pinfunction "VCC_1") (pintype "bidirectional"))
      (node (ref "U6") (pin "1") (pinfunction "VCC_1") (pintype "bidirectional"))
    )
    (net (code "104") (name "GND") (class "Default")
      (node (ref "C1") (pin "2") (pinfunction "2_2") (pintype "passive"))
      (node (ref "C11") (pin "2") (pinfunction "2_2") (pintype "passive"))
      (node (ref "C2") (pin "2") (pinfunction "2_2") (pintype "passive"))
      (node (ref "C3") (pin "2") (pinfunction "2_2") (pintype "passive"))
      (node (ref "C4") (pin "2") (pinfunction "2_2") (pintype "passive"))
      (node (ref "C5") (pin "2") (pinfunction "2_2") (pintype "passive"))
      (node (ref "C6") (pin "2") (pinfunction "2_2") (pintype "passive"))
      (node (ref "C7") (pin "2") (pinfunction "2_2") (pintype "passive"))
      (node (ref "CONF") (pin "1") (pinfunction "1_1") (pintype "passive"))
      (node (ref "CONFA") (pin "1") (pinfunction "1_1") (pintype "passive"))
      (node (ref "ENCODER") (pin "8") (pinfunction "8_8") (pintype "passive"))
      (node (ref "GPI1") (pin "1") (pinfunction "1_1") (pintype "passive"))
      (node (ref "GPO2") (pin "1") (pinfunction "1_1") (pintype "passive"))
      (node (ref "GPO3") (pin "1") (pinfunction "1_1") (pintype "passive"))
      (node (ref "IC2") (pin "14") (pinfunction "AGND_14") (pintype "power_in"))
      (node (ref "IC2") (pin "9") (pinfunction "GND_9") (pintype "power_in"))
      (node (ref "IC3") (pin "14") (pinfunction "AGND_14") (pintype "power_in"))
      (node (ref "IC3") (pin "9") (pinfunction "GND_9") (pintype "power_in"))
      (node (ref "JOYSTICKS") (pin "8") (pinfunction "8_8") (pintype "passive"))
      (node (ref "JP8") (pin "1") (pinfunction "1_1") (pintype "passive"))
      (node (ref "RESET") (pin "1") (pinfunction "1_1") (pintype "passive"))
      (node (ref "RESETA") (pin "1") (pinfunction "1_1") (pintype "passive"))
      (node (ref "SERIAL") (pin "1") (pinfunction "1_1") (pintype "passive"))
      (node (ref "SERIAL2") (pin "1") (pinfunction "1_1") (pintype "passive"))
      (node (ref "TOUCH") (pin "10") (pinfunction "10_10") (pintype "passive"))
      (node (ref "U$1") (pin "P$1") (pinfunction "1_P$1") (pintype "passive"))
      (node (ref "U$15") (pin "K1") (pinfunction "P$1_K1") (pintype "bidirectional"))
      (node (ref "U$20") (pin "P$1") (pinfunction "1_P$1") (pintype "passive"))
      (node (ref "U$35") (pin "4") (pinfunction "VSS_4") (pintype "power_in"))
      (node (ref "U1") (pin "GND@0") (pinfunction "GND_GND@0") (pintype "bidirectional"))
      (node (ref "U1") (pin "GND@1") (pinfunction "GND_GND@1") (pintype "bidirectional"))
      (node (ref "U1") (pin "GND@2") (pinfunction "GND_GND@2") (pintype "bidirectional"))
      (node (ref "U1") (pin "GND@3") (pinfunction "GND_GND@3") (pintype "bidirectional"))
      (node (ref "U1") (pin "GND@4") (pinfunction "GND_GND@4") (pintype "bidirectional"))
      (node (ref "U2") (pin "8") (pinfunction "GND_8") (pintype "bidirectional"))
      (node (ref "U3") (pin "8") (pinfunction "GND_8") (pintype "bidirectional"))
      (node (ref "U4") (pin "8") (pinfunction "GND_8") (pintype "bidirectional"))
      (node (ref "U5") (pin "8") (pinfunction "GND_8") (pintype "bidirectional"))
      (node (ref "U6") (pin "8") (pinfunction "GND_8") (pintype "bidirectional"))
      (node (ref "UART1") (pin "5") (pinfunction "5_5") (pintype "passive"))
      (node (ref "UART2") (pin "5") (pinfunction "5_5") (pintype "passive"))
      (node (ref "UART3") (pin "5") (pinfunction "5_5") (pintype "passive"))
    )
    (net (code "105") (name "Net-(SJ1-Pad1)") (class "Default")
      (node (ref "SJ1") (pin "1") (pinfunction "1_1") (pintype "passive"))
      (node (ref "UART1") (pin "10") (pinfunction "10_10") (pintype "passive"))
    )
    (net (code "106") (name "Net-(SJ2-Pad2)") (class "Default")
      (node (ref "SJ2") (pin "2") (pinfunction "2_2") (pintype "passive"))
      (node (ref "UART1") (pin "9") (pinfunction "9_9") (pintype "passive"))
    )
    (net (code "107") (name "Net-(SJ3-Pad2)") (class "Default")
      (node (ref "SJ3") (pin "2") (pinfunction "2_2") (pintype "passive"))
      (node (ref "UART2") (pin "9") (pinfunction "9_9") (pintype "passive"))
    )
    (net (code "108") (name "Net-(SJ4-Pad1)") (class "Default")
      (node (ref "SJ4") (pin "1") (pinfunction "1_1") (pintype "passive"))
      (node (ref "UART2") (pin "10") (pinfunction "10_10") (pintype "passive"))
    )
    (net (code "109") (name "Net-(SJ5-Pad1)") (class "Default")
      (node (ref "SJ5") (pin "1") (pinfunction "1_1") (pintype "passive"))
      (node (ref "UART3") (pin "10") (pinfunction "10_10") (pintype "passive"))
    )
    (net (code "110") (name "Net-(SJ6-Pad2)") (class "Default")
      (node (ref "SJ6") (pin "2") (pinfunction "2_2") (pintype "passive"))
      (node (ref "UART3") (pin "9") (pinfunction "9_9") (pintype "passive"))
    )
    (net (code "111") (name "Net-(U$15-P$2)") (class "Default")
      (node (ref "R8") (pin "1") (pinfunction "1_1") (pintype "passive"))
      (node (ref "TOUCH") (pin "2") (pinfunction "2_2") (pintype "passive"))
      (node (ref "U$15") (pin "A2") (pinfunction "P$2_A2") (pintype "bidirectional"))
    )
    (net (code "112") (name "Net-(U$15-P$3)") (class "Default")
      (node (ref "R7") (pin "1") (pinfunction "1_1") (pintype "passive"))
      (node (ref "TOUCH") (pin "6") (pinfunction "6_6") (pintype "passive"))
      (node (ref "U$15") (pin "A3") (pinfunction "P$3_A3") (pintype "bidirectional"))
    )
    (net (code "113") (name "unconnected-(JP1-Pad1)") (class "Default")
      (node (ref "JP1") (pin "1") (pinfunction "1_1") (pintype "passive"))
    )
    (net (code "114") (name "unconnected-(JP1-Pad2)") (class "Default")
      (node (ref "JP1") (pin "2") (pinfunction "2_2") (pintype "passive"))
    )
    (net (code "115") (name "unconnected-(U1-0(RX0)-Pad0)") (class "Default")
      (node (ref "U1") (pin "0") (pinfunction "0(RX0)_0") (pintype "bidirectional"))
    )
    (net (code "116") (name "unconnected-(U1-1(TX0)-Pad1)") (class "Default")
      (node (ref "U1") (pin "1") (pinfunction "1(TX0)_1") (pintype "bidirectional"))
    )
    (net (code "117") (name "unconnected-(U1-A0(RX0)-PadA0)") (class "Default")
      (node (ref "U1") (pin "A0") (pinfunction "A0(RX0)_A0") (pintype "bidirectional"))
    )
    (net (code "118") (name "unconnected-(U1-A1(TX0)-PadA1)") (class "Default")
      (node (ref "U1") (pin "A1") (pinfunction "A1(TX0)_A1") (pintype "bidirectional"))
    )
    (net (code "119") (name "unconnected-(U1-Pad10)") (class "Default")
      (node (ref "U1") (pin "10") (pinfunction "10_10") (pintype "bidirectional"))
    )
    (net (code "120") (name "unconnected-(U1-Pad11)") (class "Default")
      (node (ref "U1") (pin "11") (pinfunction "11_11") (pintype "bidirectional"))
    )
    (net (code "121") (name "unconnected-(U1-Pad12)") (class "Default")
      (node (ref "U1") (pin "12") (pinfunction "12_12") (pintype "bidirectional"))
    )
    (net (code "122") (name "unconnected-(U1-Pad13)") (class "Default")
      (node (ref "U1") (pin "13") (pinfunction "13_13") (pintype "bidirectional"))
    )
    (net (code "123") (name "unconnected-(U1-PadA2)") (class "Default")
      (node (ref "U1") (pin "A2") (pinfunction "A2_A2") (pintype "bidirectional"))
    )
    (net (code "124") (name "unconnected-(U1-PadA3)") (class "Default")
      (node (ref "U1") (pin "A3") (pinfunction "A3_A3") (pintype "bidirectional"))
    )
    (net (code "125") (name "unconnected-(U1-PadA4)") (class "Default")
      (node (ref "U1") (pin "A4") (pinfunction "A4_A4") (pintype "bidirectional"))
    )
    (net (code "126") (name "unconnected-(U1-PadA5)") (class "Default")
      (node (ref "U1") (pin "A5") (pinfunction "A5_A5") (pintype "bidirectional"))
    )
    (net (code "127") (name "unconnected-(U1-PadA10)") (class "Default")
      (node (ref "U1") (pin "A10") (pinfunction "A10_A10") (pintype "bidirectional"))
    )
    (net (code "128") (name "unconnected-(U1-PadA11)") (class "Default")
      (node (ref "U1") (pin "A11") (pinfunction "A11_A11") (pintype "bidirectional"))
    )
    (net (code "129") (name "unconnected-(U1-PadA12)") (class "Default")
      (node (ref "U1") (pin "A12") (pinfunction "A12_A12") (pintype "bidirectional"))
    )
    (net (code "130") (name "unconnected-(U1-PadA13)") (class "Default")
      (node (ref "U1") (pin "A13") (pinfunction "A13_A13") (pintype "bidirectional"))
    )
    (net (code "131") (name "unconnected-(U1-PadA14)") (class "Default")
      (node (ref "U1") (pin "A14") (pinfunction "A14_A14") (pintype "bidirectional"))
    )
    (net (code "132") (name "unconnected-(U1-PadA15)") (class "Default")
      (node (ref "U1") (pin "A15") (pinfunction "A15_A15") (pintype "bidirectional"))
    )
    (net (code "133") (name "unconnected-(U1-PadAREF)") (class "Default")
      (node (ref "U1") (pin "AREF") (pinfunction "AREF_AREF") (pintype "bidirectional"))
    )
    (net (code "134") (name "unconnected-(U2-3A-Pad7)") (class "Default")
      (node (ref "U2") (pin "7") (pinfunction "3A_7") (pintype "bidirectional"))
    )
    (net (code "135") (name "unconnected-(U2-3Y-Pad6)") (class "Default")
      (node (ref "U2") (pin "6") (pinfunction "3Y_6") (pintype "bidirectional"))
    )
    (net (code "136") (name "unconnected-(U2-4A-Pad9)") (class "Default")
      (node (ref "U2") (pin "9") (pinfunction "4A_9") (pintype "bidirectional"))
    )
    (net (code "137") (name "unconnected-(U2-4Y-Pad10)") (class "Default")
      (node (ref "U2") (pin "10") (pinfunction "4Y_10") (pintype "bidirectional"))
    )
    (net (code "138") (name "unconnected-(U6-5A-Pad11)") (class "Default")
      (node (ref "U6") (pin "11") (pinfunction "5A_11") (pintype "bidirectional"))
    )
    (net (code "139") (name "unconnected-(U6-5Y-Pad12)") (class "Default")
      (node (ref "U6") (pin "12") (pinfunction "5Y_12") (pintype "bidirectional"))
    )
    (net (code "140") (name "unconnected-(UART1-Pad1)") (class "Default")
      (node (ref "UART1") (pin "1") (pinfunction "1_1") (pintype "passive"))
    )
    (net (code "141") (name "unconnected-(UART1-Pad4)") (class "Default")
      (node (ref "UART1") (pin "4") (pinfunction "4_4") (pintype "passive"))
    )
    (net (code "142") (name "unconnected-(UART1-Pad6)") (class "Default")
      (node (ref "UART1") (pin "6") (pinfunction "6_6") (pintype "passive"))
    )
    (net (code "143") (name "unconnected-(UART1-Pad7)") (class "Default")
      (node (ref "UART1") (pin "7") (pinfunction "7_7") (pintype "passive"))
    )
    (net (code "144") (name "unconnected-(UART1-Pad8)") (class "Default")
      (node (ref "UART1") (pin "8") (pinfunction "8_8") (pintype "passive"))
    )
    (net (code "145") (name "unconnected-(UART2-Pad1)") (class "Default")
      (node (ref "UART2") (pin "1") (pinfunction "1_1") (pintype "passive"))
    )
    (net (code "146") (name "unconnected-(UART2-Pad4)") (class "Default")
      (node (ref "UART2") (pin "4") (pinfunction "4_4") (pintype "passive"))
    )
    (net (code "147") (name "unconnected-(UART2-Pad6)") (class "Default")
      (node (ref "UART2") (pin "6") (pinfunction "6_6") (pintype "passive"))
    )
    (net (code "148") (name "unconnected-(UART2-Pad7)") (class "Default")
      (node (ref "UART2") (pin "7") (pinfunction "7_7") (pintype "passive"))
    )
    (net (code "149") (name "unconnected-(UART2-Pad8)") (class "Default")
      (node (ref "UART2") (pin "8") (pinfunction "8_8") (pintype "passive"))
    )
    (net (code "150") (name "unconnected-(UART3-Pad1)") (class "Default")
      (node (ref "UART3") (pin "1") (pinfunction "1_1") (pintype "passive"))
    )
    (net (code "151") (name "unconnected-(UART3-Pad4)") (class "Default")
      (node (ref "UART3") (pin "4") (pinfunction "4_4") (pintype "passive"))
    )
    (net (code "152") (name "unconnected-(UART3-Pad6)") (class "Default")
      (node (ref "UART3") (pin "6") (pinfunction "6_6") (pintype "passive"))
    )
    (net (code "153") (name "unconnected-(UART3-Pad7)") (class "Default")
      (node (ref "UART3") (pin "7") (pinfunction "7_7") (pintype "passive"))
    )
    (net (code "154") (name "unconnected-(UART3-Pad8)") (class "Default")
      (node (ref "UART3") (pin "8") (pinfunction "8_8") (pintype "passive"))
    )
  )
)
